# tapecleaner.net
KiCad netlist of a schematic drawn in EAGLE
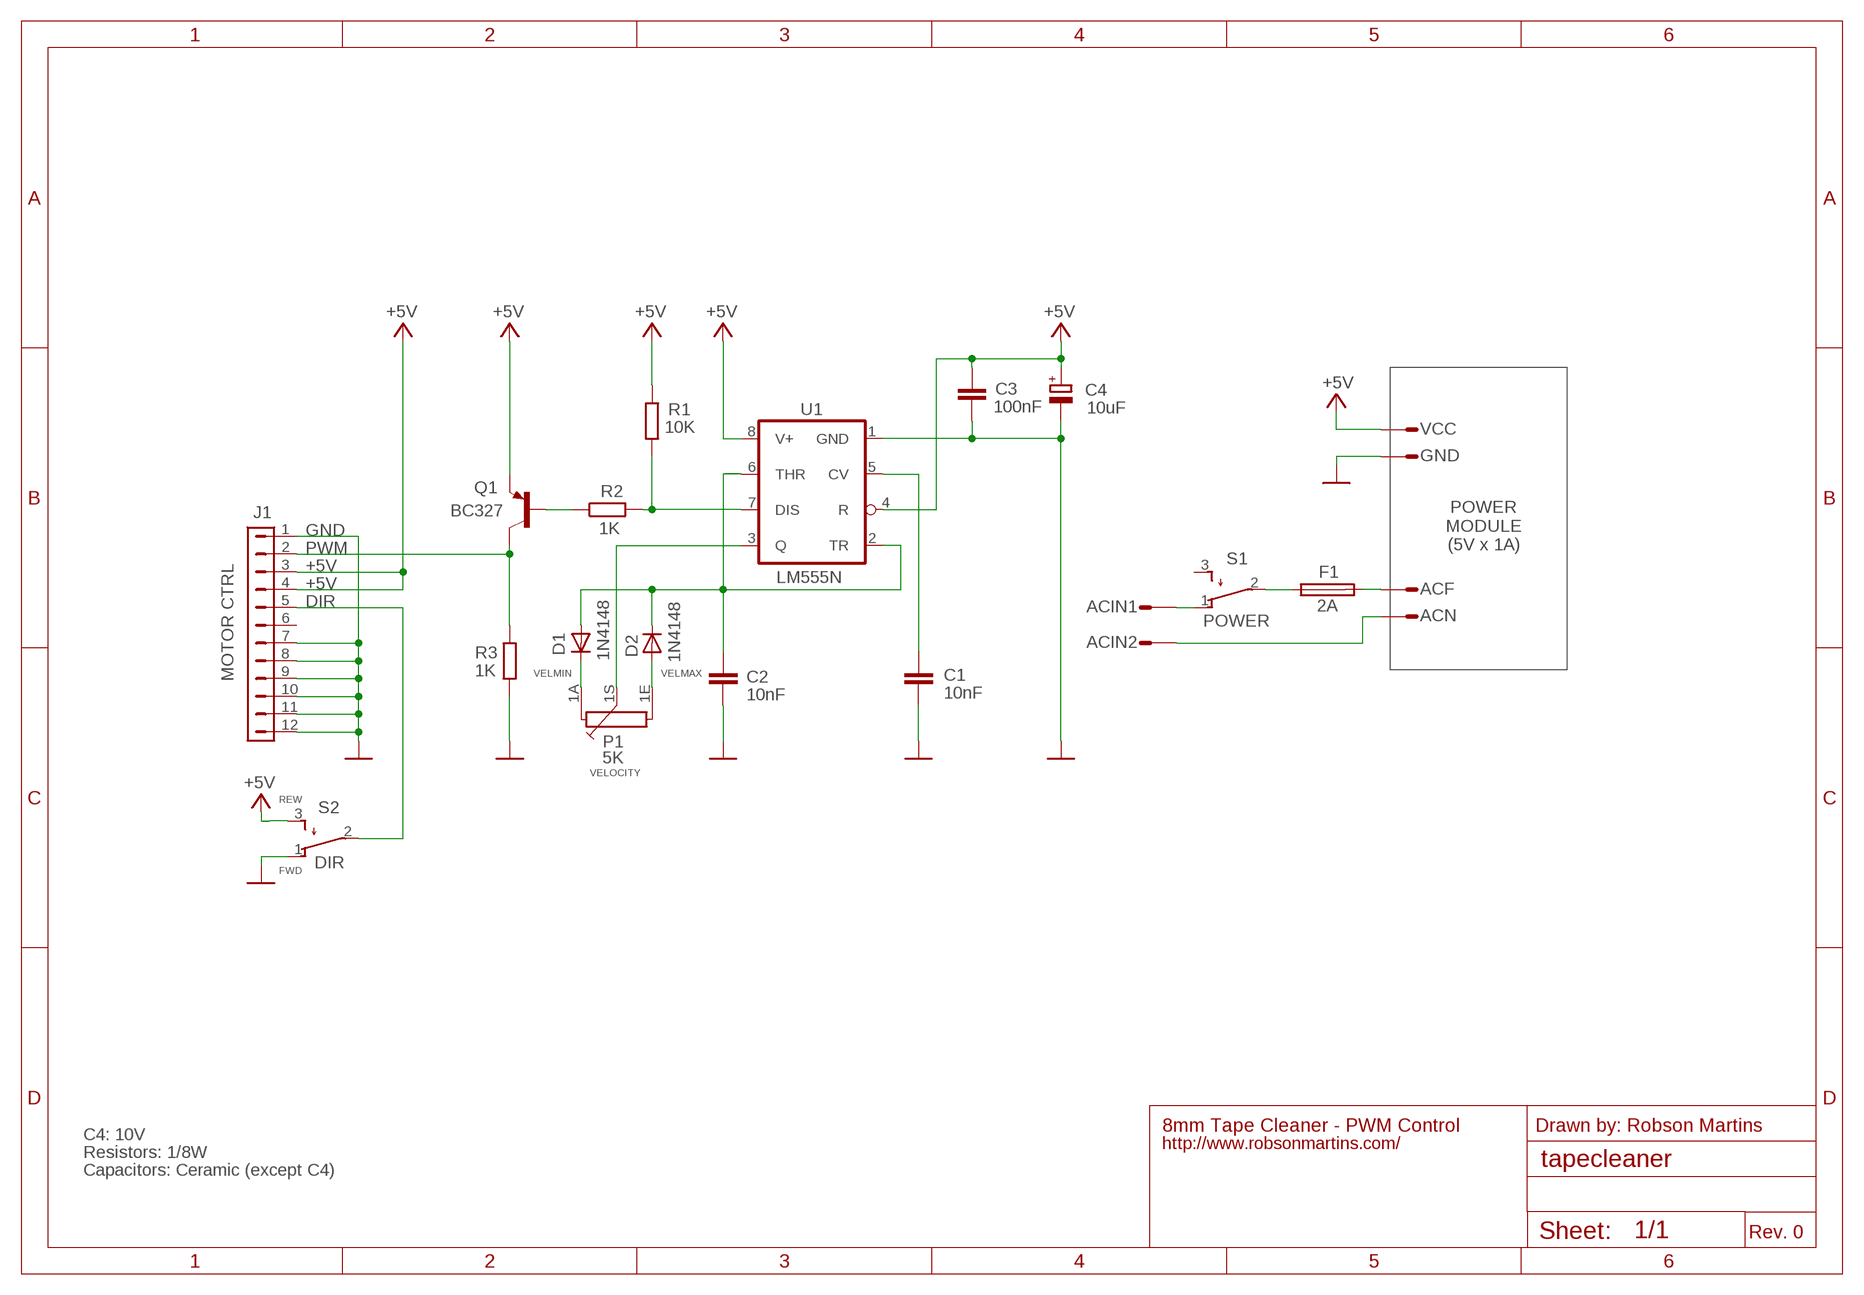
[diagram p0: schematic, sheet 1]

(export (version "E")
  (design (tool "Eeschema 10.0.6"))
  (components
    (comp (ref "ACF")
      (value "ST2,8")
      (footprint "eagle-import:ST2,8")
      (fields (field (name "OC_FARNELL") "unknown") (field (name "OC_NEWARK") "unknown"))
      (libsource (lib "eagle-import") (part "ST2,8"))
    )
    (comp (ref "ACIN1")
      (value "ST2,8")
      (footprint "eagle-import:ST2,8")
      (fields (field (name "OC_FARNELL") "unknown") (field (name "OC_NEWARK") "unknown"))
      (libsource (lib "eagle-import") (part "ST2,8"))
    )
    (comp (ref "ACIN2")
      (value "ST2,8")
      (footprint "eagle-import:ST2,8")
      (fields (field (name "OC_FARNELL") "unknown") (field (name "OC_NEWARK") "unknown"))
      (libsource (lib "eagle-import") (part "ST2,8"))
    )
    (comp (ref "ACN")
      (value "ST2,8")
      (footprint "eagle-import:ST2,8")
      (fields (field (name "OC_FARNELL") "unknown") (field (name "OC_NEWARK") "unknown"))
      (libsource (lib "eagle-import") (part "ST2,8"))
    )
    (comp (ref "C1")
      (value "10nF")
      (footprint "eagle-import:C050-025X075")
      (libsource (lib "eagle-import") (part "C-EU050-025X075"))
    )
    (comp (ref "C2")
      (value "10nF")
      (footprint "eagle-import:C050-025X075")
      (libsource (lib "eagle-import") (part "C-EU050-025X075"))
    )
    (comp (ref "C3")
      (value "100nF")
      (footprint "eagle-import:C050-025X075")
      (libsource (lib "eagle-import") (part "C-EU050-025X075"))
    )
    (comp (ref "C4")
      (value "10uF")
      (footprint "eagle-import:E2,5-6E")
      (libsource (lib "eagle-import") (part "CPOL-EUE2,5-6E"))
    )
    (comp (ref "D1")
      (value "1N4148")
      (footprint "eagle-import:DO35-7")
      (libsource (lib "eagle-import") (part "1N4148DO35-7"))
    )
    (comp (ref "D2")
      (value "1N4148")
      (footprint "eagle-import:DO35-7")
      (libsource (lib "eagle-import") (part "1N4148DO35-7"))
    )
    (comp (ref "F1")
      (value "2A")
      (footprint "eagle-import:SHK20L")
      (libsource (lib "eagle-import") (part "FUSESHK20L"))
    )
    (comp (ref "GND")
      (value "ST2,8")
      (footprint "eagle-import:ST2,8")
      (fields (field (name "OC_FARNELL") "unknown") (field (name "OC_NEWARK") "unknown"))
      (libsource (lib "eagle-import") (part "ST2,8"))
    )
    (comp (ref "J1")
      (value "MOTOR CTRL")
      (footprint "eagle-import:FH21-12S-1DSA")
      (libsource (lib "eagle-import") (part "FH21-12S-1DSA"))
    )
    (comp (ref "P1")
      (value "5K")
      (footprint "eagle-import:PC16S")
      (libsource (lib "eagle-import") (part "PC16S"))
    )
    (comp (ref "Q1")
      (value "BC327")
      (footprint "eagle-import:TO92")
      (libsource (lib "eagle-import") (part "BC327"))
    )
    (comp (ref "R1")
      (value "10K")
      (footprint "eagle-import:0204_7")
      (libsource (lib "eagle-import") (part "R-EU_0204/7"))
    )
    (comp (ref "R2")
      (value "1K")
      (footprint "eagle-import:0204_7")
      (libsource (lib "eagle-import") (part "R-EU_0204/7"))
    )
    (comp (ref "R3")
      (value "1K")
      (footprint "eagle-import:0204_7")
      (libsource (lib "eagle-import") (part "R-EU_0204/7"))
    )
    (comp (ref "S1")
      (value "POWER")
      (footprint "eagle-import:TL3XWO")
      (libsource (lib "eagle-import") (part "TL32WO"))
    )
    (comp (ref "S2")
      (value "DIR")
      (footprint "eagle-import:TL3XWO")
      (libsource (lib "eagle-import") (part "TL32WO"))
    )
    (comp (ref "U1")
      (value "LM555N")
      (footprint "eagle-import:DIL08")
      (libsource (lib "eagle-import") (part "555NLM"))
    )
    (comp (ref "VCC")
      (value "ST2,8")
      (footprint "eagle-import:ST2,8")
      (fields (field (name "OC_FARNELL") "unknown") (field (name "OC_NEWARK") "unknown"))
      (libsource (lib "eagle-import") (part "ST2,8"))
    )
  )
  (nets
    (net (code "1") (name "+5V") (class "Default")
      (node (ref "C3") (pin "1") (pinfunction "1_1") (pintype "passive"))
      (node (ref "C4") (pin "+") (pinfunction "+_+") (pintype "passive"))
      (node (ref "J1") (pin "3") (pinfunction "3_3") (pintype "passive"))
      (node (ref "J1") (pin "4") (pinfunction "4_4") (pintype "passive"))
      (node (ref "Q1") (pin "1") (pinfunction "E_1") (pintype "passive"))
      (node (ref "R1") (pin "1") (pinfunction "1_1") (pintype "passive"))
      (node (ref "S2") (pin "3") (pinfunction "S_3") (pintype "passive"))
      (node (ref "U1") (pin "4") (pinfunction "R_4") (pintype "input"))
      (node (ref "U1") (pin "8") (pinfunction "V+_8") (pintype "power_in"))
      (node (ref "VCC") (pin "1") (pinfunction "ST_1") (pintype "passive"))
    )
    (net (code "2") (name "/DIR") (class "Default")
      (node (ref "J1") (pin "5") (pinfunction "5_5") (pintype "passive"))
      (node (ref "S2") (pin "2") (pinfunction "P_2") (pintype "passive"))
    )
    (net (code "3") (name "/PWM") (class "Default")
      (node (ref "J1") (pin "2") (pinfunction "2_2") (pintype "passive"))
      (node (ref "Q1") (pin "3") (pinfunction "C_3") (pintype "passive"))
      (node (ref "R3") (pin "1") (pinfunction "1_1") (pintype "passive"))
    )
    (net (code "4") (name "/VELMAX") (class "Default")
      (node (ref "D2") (pin "A") (pinfunction "A_A") (pintype "passive"))
      (node (ref "P1") (pin "1E") (pinfunction "1E_1E") (pintype "passive"))
    )
    (net (code "5") (name "/VELMIN") (class "Default")
      (node (ref "D1") (pin "C") (pinfunction "C_C") (pintype "passive"))
      (node (ref "P1") (pin "1A") (pinfunction "1A_1A") (pintype "passive"))
    )
    (net (code "6") (name "GND") (class "Default")
      (node (ref "C1") (pin "2") (pinfunction "2_2") (pintype "passive"))
      (node (ref "C2") (pin "2") (pinfunction "2_2") (pintype "passive"))
      (node (ref "C3") (pin "2") (pinfunction "2_2") (pintype "passive"))
      (node (ref "C4") (pin "-") (pinfunction "-_-") (pintype "passive"))
      (node (ref "GND") (pin "1") (pinfunction "ST_1") (pintype "passive"))
      (node (ref "J1") (pin "1") (pinfunction "1_1") (pintype "passive"))
      (node (ref "J1") (pin "10") (pinfunction "10_10") (pintype "passive"))
      (node (ref "J1") (pin "11") (pinfunction "11_11") (pintype "passive"))
      (node (ref "J1") (pin "12") (pinfunction "12_12") (pintype "passive"))
      (node (ref "J1") (pin "7") (pinfunction "7_7") (pintype "passive"))
      (node (ref "J1") (pin "8") (pinfunction "8_8") (pintype "passive"))
      (node (ref "J1") (pin "9") (pinfunction "9_9") (pintype "passive"))
      (node (ref "R3") (pin "2") (pinfunction "2_2") (pintype "passive"))
      (node (ref "S2") (pin "1") (pinfunction "O_1") (pintype "passive"))
      (node (ref "U1") (pin "1") (pinfunction "GND_1") (pintype "power_in"))
    )
    (net (code "7") (name "Net-(ACF-ST)") (class "Default")
      (node (ref "ACF") (pin "1") (pinfunction "ST_1") (pintype "passive"))
      (node (ref "F1") (pin "2A") (pinfunction "2_2A") (pintype "passive"))
    )
    (net (code "8") (name "Net-(ACIN1-ST)") (class "Default")
      (node (ref "ACIN1") (pin "1") (pinfunction "ST_1") (pintype "passive"))
      (node (ref "S1") (pin "1") (pinfunction "O_1") (pintype "passive"))
    )
    (net (code "9") (name "Net-(ACIN2-ST)") (class "Default")
      (node (ref "ACIN2") (pin "1") (pinfunction "ST_1") (pintype "passive"))
      (node (ref "ACN") (pin "1") (pinfunction "ST_1") (pintype "passive"))
    )
    (net (code "10") (name "Net-(F1-1)") (class "Default")
      (node (ref "F1") (pin "1A") (pinfunction "1_1A") (pintype "passive"))
      (node (ref "S1") (pin "2") (pinfunction "P_2") (pintype "passive"))
    )
    (net (code "11") (name "Net-(Q1-B)") (class "Default")
      (node (ref "Q1") (pin "2") (pinfunction "B_2") (pintype "passive"))
      (node (ref "R2") (pin "1") (pinfunction "1_1") (pintype "passive"))
    )
    (net (code "12") (name "Net-(U1-CV)") (class "Default")
      (node (ref "C1") (pin "1") (pinfunction "1_1") (pintype "passive"))
      (node (ref "U1") (pin "5") (pinfunction "CV_5") (pintype "input"))
    )
    (net (code "13") (name "Net-(U1-DIS)") (class "Default")
      (node (ref "R1") (pin "2") (pinfunction "2_2") (pintype "passive"))
      (node (ref "R2") (pin "2") (pinfunction "2_2") (pintype "passive"))
      (node (ref "U1") (pin "7") (pinfunction "DIS_7") (pintype "input"))
    )
    (net (code "14") (name "Net-(U1-Q)") (class "Default")
      (node (ref "P1") (pin "1S") (pinfunction "1S_1S") (pintype "passive"))
      (node (ref "U1") (pin "3") (pinfunction "Q_3") (pintype "output"))
    )
    (net (code "15") (name "Net-(U1-THR)") (class "Default")
      (node (ref "C2") (pin "1") (pinfunction "1_1") (pintype "passive"))
      (node (ref "D1") (pin "A") (pinfunction "A_A") (pintype "passive"))
      (node (ref "D2") (pin "C") (pinfunction "C_C") (pintype "passive"))
      (node (ref "U1") (pin "2") (pinfunction "TR_2") (pintype "input"))
      (node (ref "U1") (pin "6") (pinfunction "THR_6") (pintype "input"))
    )
    (net (code "16") (name "unconnected-(J1-Pad6)") (class "Default")
      (node (ref "J1") (pin "6") (pinfunction "6_6") (pintype "passive"))
    )
    (net (code "17") (name "unconnected-(S1-S-Pad3)") (class "Default")
      (node (ref "S1") (pin "3") (pinfunction "S_3") (pintype "passive"))
    )
  )
)
